# SCH_Research-Project_2024-03-13.net
KiCad netlist of a schematic drawn in EasyEDA
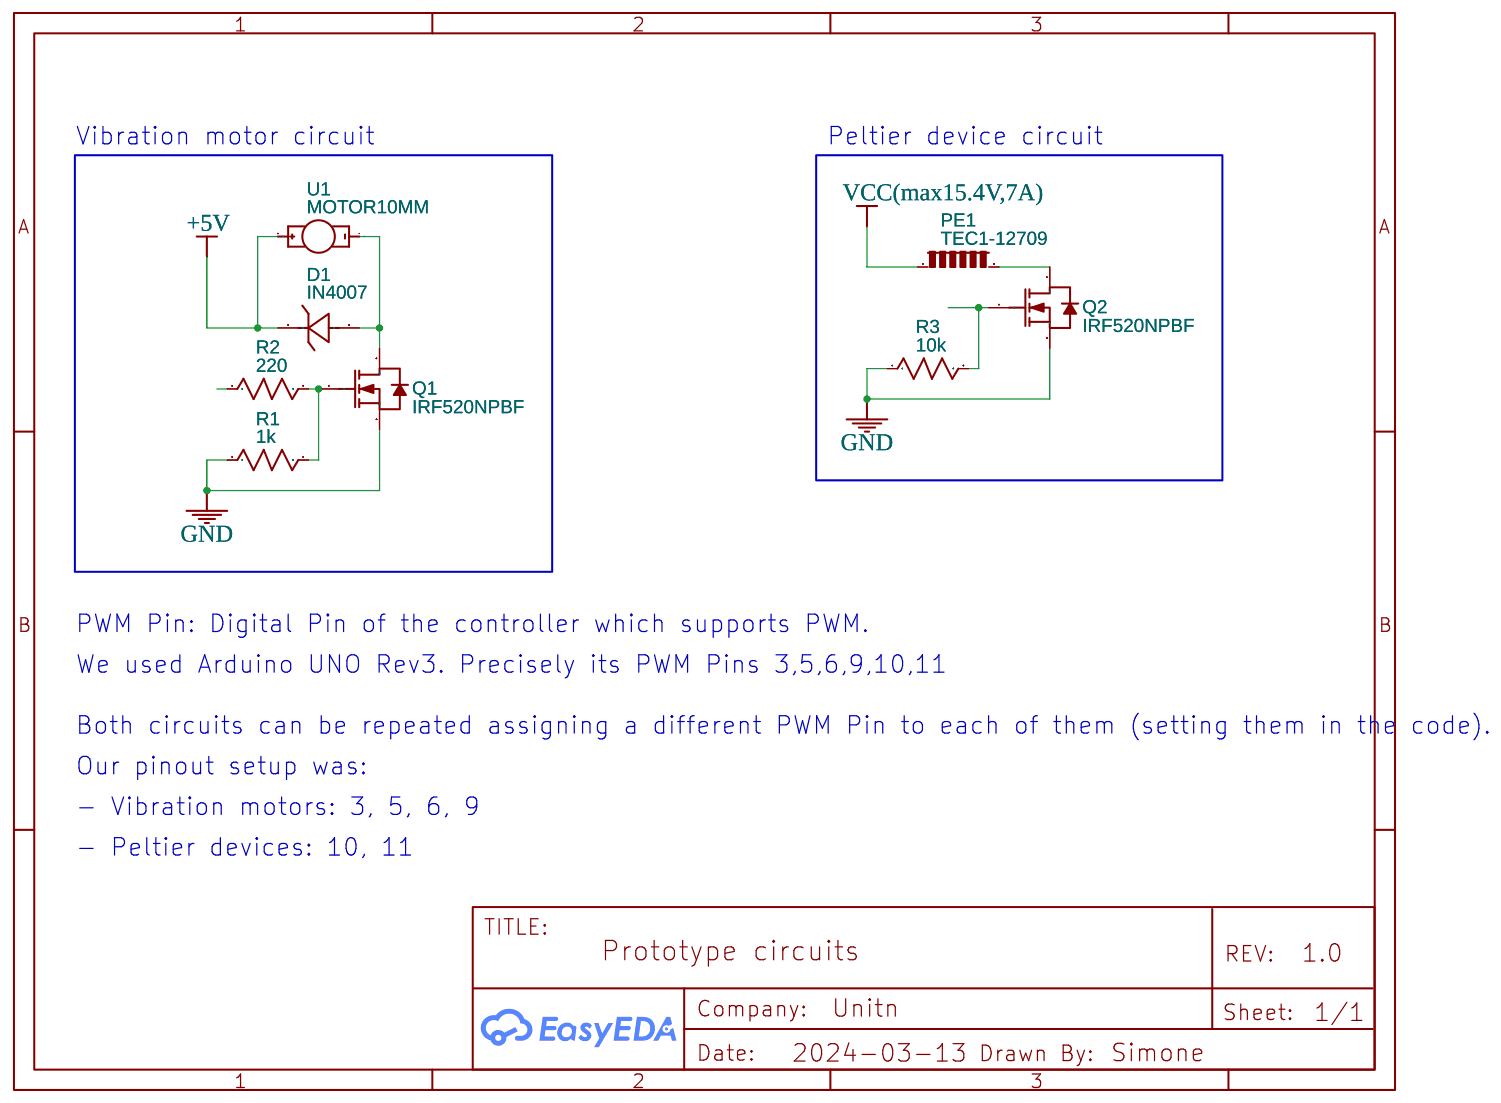
[diagram p0: schematic sheet]

(export (version "E")
  (design (tool "Eeschema 10.0.6"))
  (components
    (comp (ref "D1") (value "IN4007") (libsource (lib "") (part "IN4007")))
    (comp (ref "PE1") (value "TEC1-12709") (libsource (lib "") (part "Peltier_Element")))
    (comp (ref "Q1")
      (value "IRF520NPBF")
      (fields (field (name "Manufacturer") "Infineon(英飞凌)"))
      (libsource (lib "") (part "IRF520NPBF"))
    )
    (comp (ref "Q2")
      (value "IRF520NPBF")
      (fields (field (name "Manufacturer") "Infineon(英飞凌)"))
      (libsource (lib "") (part "IRF520NPBF"))
    )
    (comp (ref "R1") (value "1k") (libsource (lib "") (part "R_0603_US")))
    (comp (ref "R2") (value "220") (libsource (lib "") (part "R_0603_US")))
    (comp (ref "R3") (value "10k") (libsource (lib "") (part "R_0603_US")))
    (comp (ref "U1") (value "MOTOR10MM") (libsource (lib "") (part "MOTOR10MM")))
  )
  (nets
    (net (code "1") (name "+5V") (class "Default")
      (node (ref "D1") (pin "1") (pinfunction "C_1") (pintype "unspecified"))
      (node (ref "U1") (pin "+") (pinfunction "+_+") (pintype "unspecified"))
    )
    (net (code "2") (name "GND") (class "Default")
      (node (ref "Q1") (pin "3") (pinfunction "S_3") (pintype "unspecified"))
      (node (ref "Q2") (pin "3") (pinfunction "S_3") (pintype "unspecified"))
      (node (ref "R1") (pin "1") (pinfunction "1_1") (pintype "unspecified"))
      (node (ref "R3") (pin "1") (pinfunction "1_1") (pintype "unspecified"))
    )
    (net (code "3") (name "Net-(D1-A)") (class "Default")
      (node (ref "D1") (pin "2") (pinfunction "A_2") (pintype "unspecified"))
      (node (ref "Q1") (pin "2") (pinfunction "D_2") (pintype "unspecified"))
      (node (ref "U1") (pin "-") (pinfunction "-_-") (pintype "unspecified"))
    )
    (net (code "4") (name "Net-(Q1-G)") (class "Default")
      (node (ref "Q1") (pin "1") (pinfunction "G_1") (pintype "unspecified"))
      (node (ref "R1") (pin "2") (pinfunction "2_2") (pintype "unspecified"))
      (node (ref "R2") (pin "2") (pinfunction "2_2") (pintype "unspecified"))
    )
    (net (code "5") (name "Net-(Q2-D)") (class "Default")
      (node (ref "PE1") (pin "2") (pintype "unspecified"))
      (node (ref "Q2") (pin "2") (pinfunction "D_2") (pintype "unspecified"))
    )
    (net (code "6") (name "Net-(Q2-G)") (class "Default")
      (node (ref "Q2") (pin "1") (pinfunction "G_1") (pintype "unspecified"))
      (node (ref "R3") (pin "2") (pinfunction "2_2") (pintype "unspecified"))
    )
    (net (code "7") (name "VCC(max15.4V,7A)") (class "Default")
      (node (ref "PE1") (pin "1") (pintype "unspecified"))
    )
    (net (code "8") (name "unconnected-(R2-Pad1)") (class "Default")
      (node (ref "R2") (pin "1") (pinfunction "1_1") (pintype "unspecified"))
    )
  )
)
